# NanoRemotev2.net
KiCad netlist of a schematic drawn in EAGLE
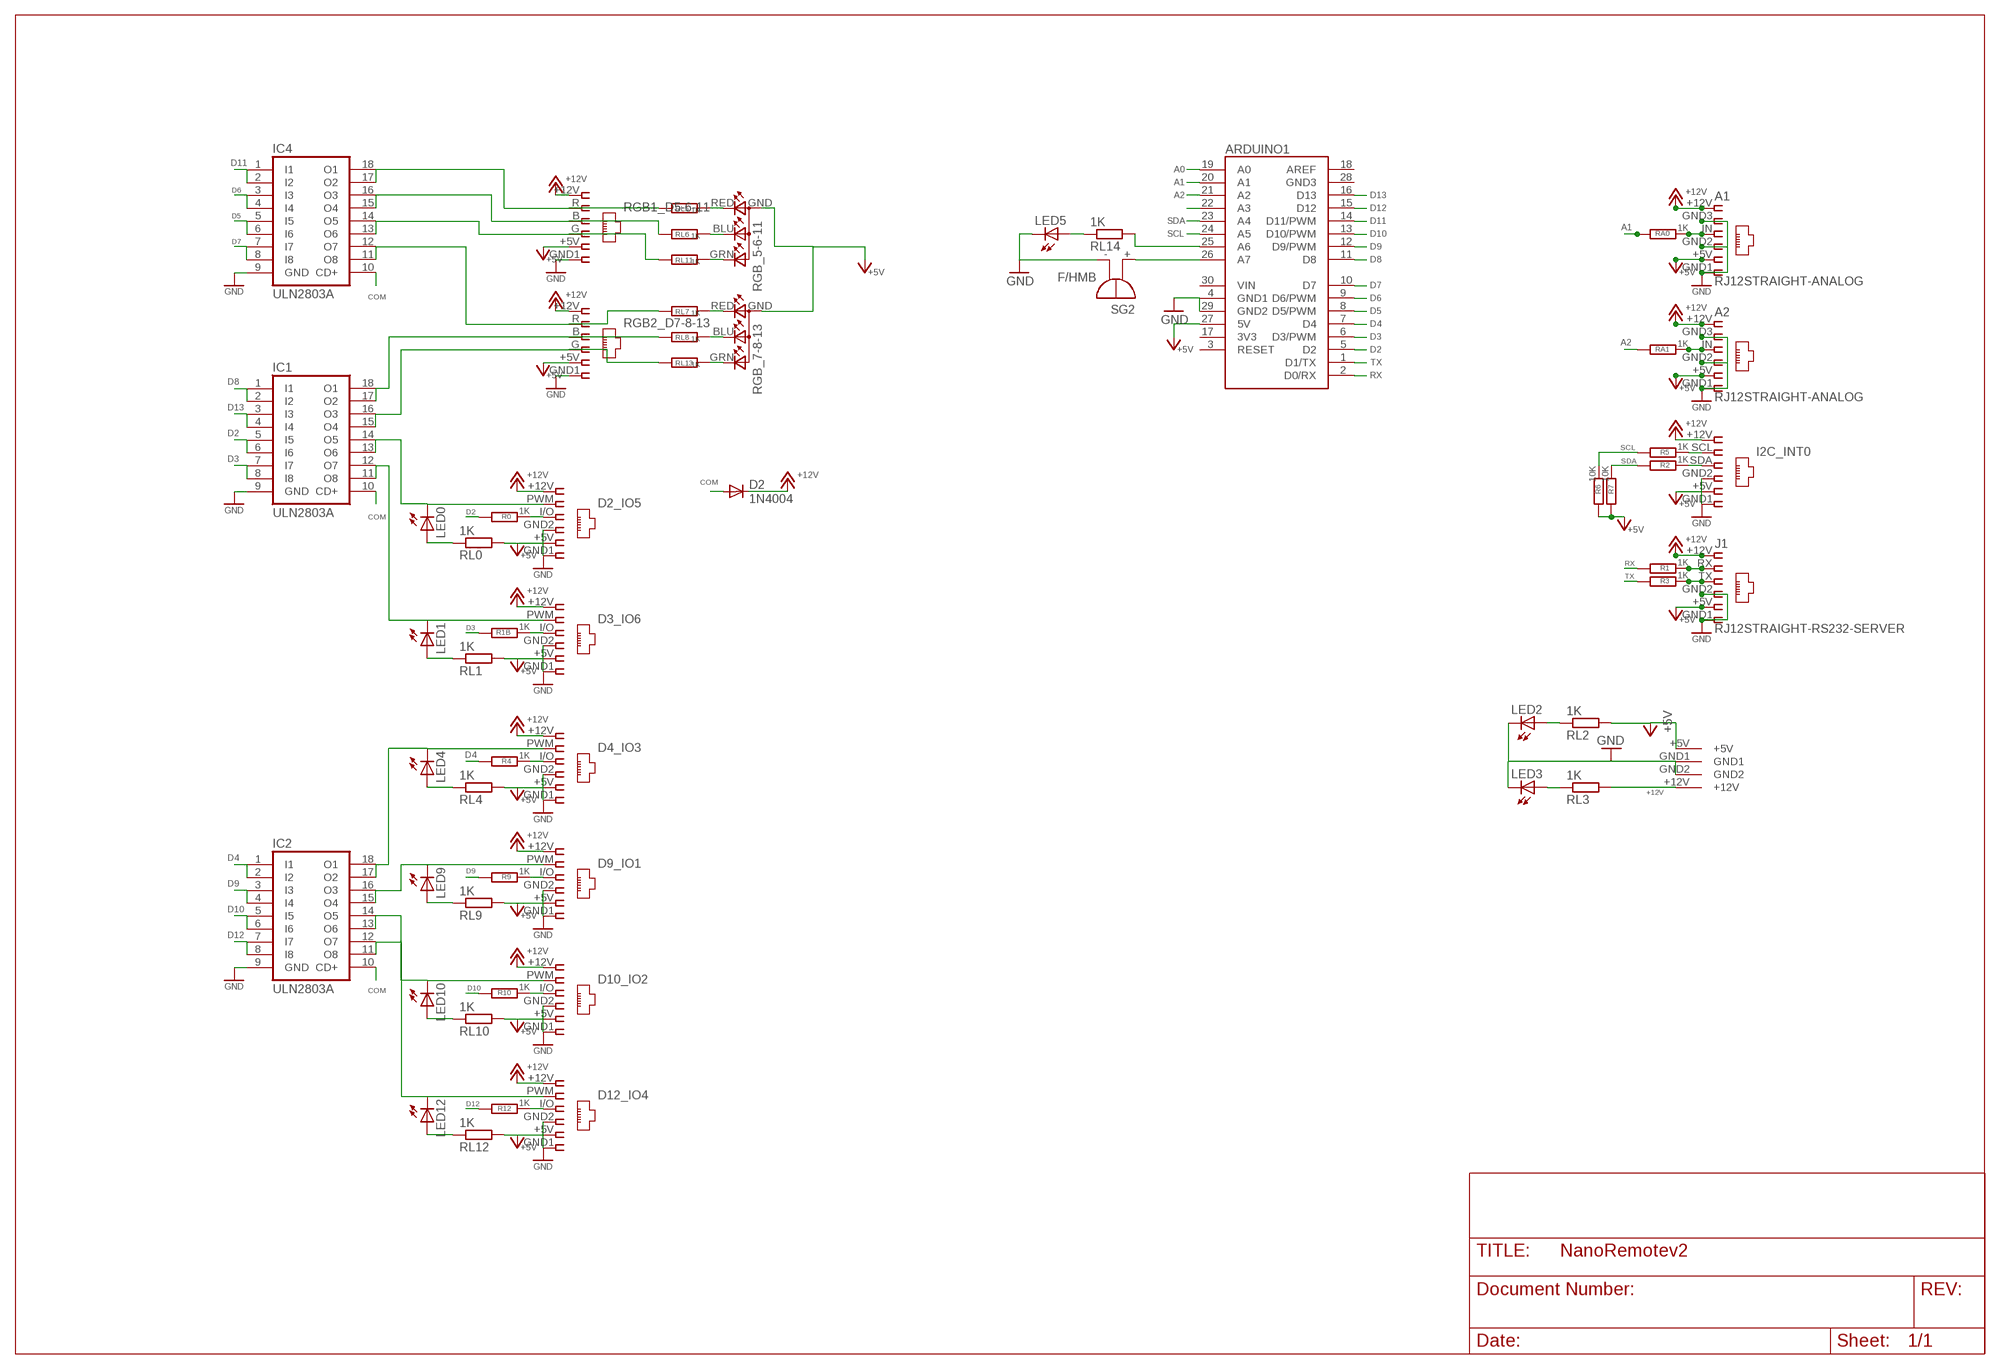
[diagram p0: schematic, sheet 1]

(export (version "E")
  (design (tool "Eeschema 10.0.6"))
  (components
    (comp (ref "A1")
      (value "RJ12STRAIGHT-ANALOG")
      (footprint "eagle-import:RJ12-STRAIGHT-ANALOG")
      (libsource (lib "eagle-import") (part "RJ12STRAIGHT-ANALOG"))
    )
    (comp (ref "A2")
      (value "RJ12STRAIGHT-ANALOG")
      (footprint "eagle-import:RJ12-STRAIGHT-ANALOG")
      (libsource (lib "eagle-import") (part "RJ12STRAIGHT-ANALOG"))
    )
    (comp (ref "ARDUINO1")
      (value "ARDUINO_NANO")
      (footprint "eagle-import:ARDUINO_NANO")
      (libsource (lib "eagle-import") (part "ARDUINO_NANO"))
    )
    (comp (ref "D2")
      (value "1N4004")
      (footprint "eagle-import:DO41-10")
      (libsource (lib "eagle-import") (part "1N4004"))
    )
    (comp (ref "D2_IO5")
      (value "IO5")
      (footprint "eagle-import:RJ12-STRAIGHT")
      (libsource (lib "eagle-import") (part "RJ12STRAIGHT"))
    )
    (comp (ref "D3_IO6")
      (value "IO6")
      (footprint "eagle-import:RJ12-STRAIGHT")
      (libsource (lib "eagle-import") (part "RJ12STRAIGHT"))
    )
    (comp (ref "D4_IO3")
      (value "IO3")
      (footprint "eagle-import:RJ12-STRAIGHT")
      (libsource (lib "eagle-import") (part "RJ12STRAIGHT"))
    )
    (comp (ref "D9_IO1")
      (value "IO1")
      (footprint "eagle-import:RJ12-STRAIGHT")
      (libsource (lib "eagle-import") (part "RJ12STRAIGHT"))
    )
    (comp (ref "D10_IO2")
      (value "IO2")
      (footprint "eagle-import:RJ12-STRAIGHT")
      (libsource (lib "eagle-import") (part "RJ12STRAIGHT"))
    )
    (comp (ref "D12_IO4")
      (value "IO4")
      (footprint "eagle-import:RJ12-STRAIGHT")
      (libsource (lib "eagle-import") (part "RJ12STRAIGHT"))
    )
    (comp (ref "I2C_INT0")
      (value "I2C")
      (footprint "eagle-import:RJ12-STRAIGHT-I2C")
      (libsource (lib "eagle-import") (part "RJ12STRAIGHT-I2C"))
    )
    (comp (ref "IC1")
      (value "ULN2803A")
      (footprint "eagle-import:SO18W")
      (libsource (lib "eagle-import") (part "ULN2803A"))
    )
    (comp (ref "IC2")
      (value "ULN2803A")
      (footprint "eagle-import:SO18W")
      (libsource (lib "eagle-import") (part "ULN2803A"))
    )
    (comp (ref "IC4")
      (value "ULN2803A")
      (footprint "eagle-import:SO18W")
      (libsource (lib "eagle-import") (part "ULN2803A"))
    )
    (comp (ref "J1")
      (value "RJ12STRAIGHT-RS232-SERVER")
      (footprint "eagle-import:RJ12-STRAIGHT-RS232")
      (libsource (lib "eagle-import") (part "RJ12STRAIGHT-RS232-SERVER"))
    )
    (comp (ref "LED0")
      (value "LED3MM")
      (footprint "eagle-import:LED3MM")
      (libsource (lib "eagle-import") (part "LED3MM"))
    )
    (comp (ref "LED1")
      (value "LED3MM")
      (footprint "eagle-import:LED3MM")
      (libsource (lib "eagle-import") (part "LED3MM"))
    )
    (comp (ref "LED2")
      (value "LED3MM")
      (footprint "eagle-import:LED3MM")
      (libsource (lib "eagle-import") (part "LED3MM"))
    )
    (comp (ref "LED3")
      (value "LED3MM")
      (footprint "eagle-import:LED3MM")
      (libsource (lib "eagle-import") (part "LED3MM"))
    )
    (comp (ref "LED4")
      (value "LED3MM")
      (footprint "eagle-import:LED3MM")
      (libsource (lib "eagle-import") (part "LED3MM"))
    )
    (comp (ref "LED5")
      (value "LED3MM")
      (footprint "eagle-import:LED3MM")
      (libsource (lib "eagle-import") (part "LED3MM"))
    )
    (comp (ref "LED9")
      (value "LED3MM")
      (footprint "eagle-import:LED3MM")
      (libsource (lib "eagle-import") (part "LED3MM"))
    )
    (comp (ref "LED10")
      (value "LED3MM")
      (footprint "eagle-import:LED3MM")
      (libsource (lib "eagle-import") (part "LED3MM"))
    )
    (comp (ref "LED12")
      (value "LED3MM")
      (footprint "eagle-import:LED3MM")
      (libsource (lib "eagle-import") (part "LED3MM"))
    )
    (comp (ref "R0")
      (value "1K")
      (footprint "eagle-import:M1206")
      (libsource (lib "eagle-import") (part "R-EU_M1206"))
    )
    (comp (ref "R1")
      (value "1K")
      (footprint "eagle-import:M1206")
      (libsource (lib "eagle-import") (part "R-EU_M1206"))
    )
    (comp (ref "R1B")
      (value "1K")
      (footprint "eagle-import:M1206")
      (libsource (lib "eagle-import") (part "R-EU_M1206"))
    )
    (comp (ref "R2")
      (value "1K")
      (footprint "eagle-import:M1206")
      (libsource (lib "eagle-import") (part "R-EU_M1206"))
    )
    (comp (ref "R3")
      (value "1K")
      (footprint "eagle-import:M1206")
      (libsource (lib "eagle-import") (part "R-EU_M1206"))
    )
    (comp (ref "R4")
      (value "1K")
      (footprint "eagle-import:M1206")
      (libsource (lib "eagle-import") (part "R-EU_M1206"))
    )
    (comp (ref "R5")
      (value "1K")
      (footprint "eagle-import:M1206")
      (libsource (lib "eagle-import") (part "R-EU_M1206"))
    )
    (comp (ref "R6")
      (value "10K")
      (footprint "eagle-import:M1206")
      (libsource (lib "eagle-import") (part "R-EU_M1206"))
    )
    (comp (ref "R7")
      (value "10K")
      (footprint "eagle-import:M1206")
      (libsource (lib "eagle-import") (part "R-EU_M1206"))
    )
    (comp (ref "R9")
      (value "1K")
      (footprint "eagle-import:M1206")
      (libsource (lib "eagle-import") (part "R-EU_M1206"))
    )
    (comp (ref "R10")
      (value "1K")
      (footprint "eagle-import:M1206")
      (libsource (lib "eagle-import") (part "R-EU_M1206"))
    )
    (comp (ref "R12")
      (value "1K")
      (footprint "eagle-import:M1206")
      (libsource (lib "eagle-import") (part "R-EU_M1206"))
    )
    (comp (ref "RA0")
      (value "1K")
      (footprint "eagle-import:M1206")
      (libsource (lib "eagle-import") (part "R-EU_M1206"))
    )
    (comp (ref "RA1")
      (value "1K")
      (footprint "eagle-import:M1206")
      (libsource (lib "eagle-import") (part "R-EU_M1206"))
    )
    (comp (ref "RGB1_D5-6-11")
      (value "RGB1")
      (footprint "eagle-import:RJ12-STRAIGHT-RGB")
      (libsource (lib "eagle-import") (part "RJ12STRAIGHT-RGB"))
    )
    (comp (ref "RGB2_D7-8-13")
      (value "RGB2")
      (footprint "eagle-import:RJ12-STRAIGHT-RGB")
      (libsource (lib "eagle-import") (part "RJ12STRAIGHT-RGB"))
    )
    (comp (ref "RGB_5-6-11")
      (value "TOPLED-3")
      (footprint "eagle-import:LED-TRICOLOR-THROUGHHOLE")
      (libsource (lib "eagle-import") (part "TOPLED-3"))
    )
    (comp (ref "RGB_7-8-13")
      (value "TOPLED-3")
      (footprint "eagle-import:LED-TRICOLOR-THROUGHHOLE")
      (libsource (lib "eagle-import") (part "TOPLED-3"))
    )
    (comp (ref "RL0")
      (value "1K")
      (footprint "eagle-import:M1206")
      (libsource (lib "eagle-import") (part "R-EU_M1206"))
    )
    (comp (ref "RL1")
      (value "1K")
      (footprint "eagle-import:M1206")
      (libsource (lib "eagle-import") (part "R-EU_M1206"))
    )
    (comp (ref "RL2")
      (value "1K")
      (footprint "eagle-import:M1206")
      (libsource (lib "eagle-import") (part "R-EU_M1206"))
    )
    (comp (ref "RL3")
      (value "1K")
      (footprint "eagle-import:M1206")
      (libsource (lib "eagle-import") (part "R-EU_M1206"))
    )
    (comp (ref "RL4")
      (value "1K")
      (footprint "eagle-import:M1206")
      (libsource (lib "eagle-import") (part "R-EU_M1206"))
    )
    (comp (ref "RL5")
      (value "1K")
      (footprint "eagle-import:M1206")
      (libsource (lib "eagle-import") (part "R-EU_M1206"))
    )
    (comp (ref "RL6")
      (value "1K")
      (footprint "eagle-import:M1206")
      (libsource (lib "eagle-import") (part "R-EU_M1206"))
    )
    (comp (ref "RL7")
      (value "1K")
      (footprint "eagle-import:M1206")
      (libsource (lib "eagle-import") (part "R-EU_M1206"))
    )
    (comp (ref "RL8")
      (value "1K")
      (footprint "eagle-import:M1206")
      (libsource (lib "eagle-import") (part "R-EU_M1206"))
    )
    (comp (ref "RL9")
      (value "1K")
      (footprint "eagle-import:M1206")
      (libsource (lib "eagle-import") (part "R-EU_M1206"))
    )
    (comp (ref "RL10")
      (value "1K")
      (footprint "eagle-import:M1206")
      (libsource (lib "eagle-import") (part "R-EU_M1206"))
    )
    (comp (ref "RL11")
      (value "1K")
      (footprint "eagle-import:M1206")
      (libsource (lib "eagle-import") (part "R-EU_M1206"))
    )
    (comp (ref "RL12")
      (value "1K")
      (footprint "eagle-import:M1206")
      (libsource (lib "eagle-import") (part "R-EU_M1206"))
    )
    (comp (ref "RL13")
      (value "1K")
      (footprint "eagle-import:M1206")
      (libsource (lib "eagle-import") (part "R-EU_M1206"))
    )
    (comp (ref "RL14")
      (value "1K")
      (footprint "eagle-import:M1206")
      (libsource (lib "eagle-import") (part "R-EU_M1206"))
    )
    (comp (ref "SG2")
      (value "F/HMB")
      (footprint "eagle-import:F_HMB")
      (libsource (lib "eagle-import") (part "F/HMB"))
    )
    (comp (ref "U$1")
      (value "KPJX-4S-S")
      (footprint "eagle-import:KPJX-4S-S")
      (libsource (lib "eagle-import") (part "KPJX-4S-S"))
    )
  )
  (nets
    (net (code "1") (name "+5V") (class "Default")
      (node (ref "A1") (pin "+5V") (pinfunction "5_+5V") (pintype "power_in"))
      (node (ref "A2") (pin "+5V") (pinfunction "5_+5V") (pintype "power_in"))
      (node (ref "ARDUINO1") (pin "27") (pinfunction "5V_27") (pintype "power_in"))
      (node (ref "D10_IO2") (pin "+5V") (pinfunction "5_+5V") (pintype "power_in"))
      (node (ref "D12_IO4") (pin "+5V") (pinfunction "5_+5V") (pintype "power_in"))
      (node (ref "D2_IO5") (pin "+5V") (pinfunction "5_+5V") (pintype "power_in"))
      (node (ref "D3_IO6") (pin "+5V") (pinfunction "5_+5V") (pintype "power_in"))
      (node (ref "D4_IO3") (pin "+5V") (pinfunction "5_+5V") (pintype "power_in"))
      (node (ref "D9_IO1") (pin "+5V") (pinfunction "5_+5V") (pintype "power_in"))
      (node (ref "I2C_INT0") (pin "+5V") (pinfunction "5_+5V") (pintype "power_in"))
      (node (ref "J1") (pin "+5V") (pinfunction "5_+5V") (pintype "power_in"))
      (node (ref "R6") (pin "2") (pinfunction "2_2") (pintype "passive"))
      (node (ref "R7") (pin "2") (pinfunction "2_2") (pintype "passive"))
      (node (ref "RGB1_D5-6-11") (pin "+5V") (pinfunction "5_+5V") (pintype "power_in"))
      (node (ref "RGB2_D7-8-13") (pin "+5V") (pinfunction "5_+5V") (pintype "power_in"))
      (node (ref "RGB_5-6-11") (pin "GND") (pinfunction "A2_GND") (pintype "passive"))
      (node (ref "RGB_7-8-13") (pin "GND") (pinfunction "A2_GND") (pintype "passive"))
      (node (ref "RL0") (pin "2") (pinfunction "2_2") (pintype "passive"))
      (node (ref "RL1") (pin "2") (pinfunction "2_2") (pintype "passive"))
      (node (ref "RL10") (pin "2") (pinfunction "2_2") (pintype "passive"))
      (node (ref "RL12") (pin "2") (pinfunction "2_2") (pintype "passive"))
      (node (ref "RL2") (pin "2") (pinfunction "2_2") (pintype "passive"))
      (node (ref "RL4") (pin "2") (pinfunction "2_2") (pintype "passive"))
      (node (ref "RL9") (pin "2") (pinfunction "2_2") (pintype "passive"))
      (node (ref "U$1") (pin "+5V") (pinfunction "+5V_+5V") (pintype "power_in"))
    )
    (net (code "2") (name "+12V") (class "Default")
      (node (ref "A1") (pin "+12V") (pinfunction "1_+12V") (pintype "power_in"))
      (node (ref "A2") (pin "+12V") (pinfunction "1_+12V") (pintype "power_in"))
      (node (ref "D10_IO2") (pin "+12V") (pinfunction "1_+12V") (pintype "power_in"))
      (node (ref "D12_IO4") (pin "+12V") (pinfunction "1_+12V") (pintype "power_in"))
      (node (ref "D2") (pin "C") (pinfunction "C_C") (pintype "passive"))
      (node (ref "D2_IO5") (pin "+12V") (pinfunction "1_+12V") (pintype "power_in"))
      (node (ref "D3_IO6") (pin "+12V") (pinfunction "1_+12V") (pintype "power_in"))
      (node (ref "D4_IO3") (pin "+12V") (pinfunction "1_+12V") (pintype "power_in"))
      (node (ref "D9_IO1") (pin "+12V") (pinfunction "1_+12V") (pintype "power_in"))
      (node (ref "I2C_INT0") (pin "+12V") (pinfunction "1_+12V") (pintype "power_in"))
      (node (ref "J1") (pin "+12V") (pinfunction "1_+12V") (pintype "power_in"))
      (node (ref "RGB1_D5-6-11") (pin "+12V") (pinfunction "1_+12V") (pintype "power_in"))
      (node (ref "RGB2_D7-8-13") (pin "+12V") (pinfunction "1_+12V") (pintype "power_in"))
      (node (ref "RL3") (pin "2") (pinfunction "2_2") (pintype "passive"))
      (node (ref "U$1") (pin "+12V") (pinfunction "+12V_+12V") (pintype "power_in"))
    )
    (net (code "3") (name "/3V3") (class "Default")
      (node (ref "ARDUINO1") (pin "17") (pinfunction "3V3_17") (pintype "power_in"))
    )
    (net (code "4") (name "/A0") (class "Default")
      (node (ref "ARDUINO1") (pin "19") (pinfunction "A0_19") (pintype "bidirectional"))
    )
    (net (code "5") (name "/A1") (class "Default")
      (node (ref "ARDUINO1") (pin "20") (pinfunction "A1_20") (pintype "bidirectional"))
      (node (ref "RA0") (pin "2") (pinfunction "2_2") (pintype "passive"))
    )
    (net (code "6") (name "/A2") (class "Default")
      (node (ref "ARDUINO1") (pin "21") (pinfunction "A2_21") (pintype "bidirectional"))
      (node (ref "RA1") (pin "2") (pinfunction "2_2") (pintype "passive"))
    )
    (net (code "7") (name "/COM") (class "Default")
      (node (ref "D2") (pin "A") (pinfunction "A_A") (pintype "passive"))
      (node (ref "IC1") (pin "10") (pinfunction "CD+_10") (pintype "passive"))
      (node (ref "IC2") (pin "10") (pinfunction "CD+_10") (pintype "passive"))
      (node (ref "IC4") (pin "10") (pinfunction "CD+_10") (pintype "passive"))
    )
    (net (code "8") (name "/D2") (class "Default")
      (node (ref "ARDUINO1") (pin "5") (pinfunction "D2_5") (pintype "bidirectional"))
      (node (ref "IC1") (pin "5") (pinfunction "I5_5") (pintype "input"))
      (node (ref "IC1") (pin "6") (pinfunction "I6_6") (pintype "input"))
      (node (ref "R0") (pin "2") (pinfunction "2_2") (pintype "passive"))
    )
    (net (code "9") (name "/D3") (class "Default")
      (node (ref "ARDUINO1") (pin "6") (pinfunction "D3/PWM_6") (pintype "bidirectional"))
      (node (ref "IC1") (pin "7") (pinfunction "I7_7") (pintype "input"))
      (node (ref "IC1") (pin "8") (pinfunction "I8_8") (pintype "input"))
      (node (ref "R1B") (pin "2") (pinfunction "2_2") (pintype "passive"))
    )
    (net (code "10") (name "/D4") (class "Default")
      (node (ref "ARDUINO1") (pin "7") (pinfunction "D4_7") (pintype "bidirectional"))
      (node (ref "IC2") (pin "1") (pinfunction "I1_1") (pintype "input"))
      (node (ref "IC2") (pin "2") (pinfunction "I2_2") (pintype "input"))
      (node (ref "R4") (pin "2") (pinfunction "2_2") (pintype "passive"))
    )
    (net (code "11") (name "/D5") (class "Default")
      (node (ref "ARDUINO1") (pin "8") (pinfunction "D5/PWM_8") (pintype "bidirectional"))
      (node (ref "IC4") (pin "5") (pinfunction "I5_5") (pintype "input"))
      (node (ref "IC4") (pin "6") (pinfunction "I6_6") (pintype "input"))
    )
    (net (code "12") (name "/D6") (class "Default")
      (node (ref "ARDUINO1") (pin "9") (pinfunction "D6/PWM_9") (pintype "bidirectional"))
      (node (ref "IC4") (pin "3") (pinfunction "I3_3") (pintype "input"))
      (node (ref "IC4") (pin "4") (pinfunction "I4_4") (pintype "input"))
    )
    (net (code "13") (name "/D7") (class "Default")
      (node (ref "ARDUINO1") (pin "10") (pinfunction "D7_10") (pintype "bidirectional"))
      (node (ref "IC4") (pin "7") (pinfunction "I7_7") (pintype "input"))
      (node (ref "IC4") (pin "8") (pinfunction "I8_8") (pintype "input"))
    )
    (net (code "14") (name "/D8") (class "Default")
      (node (ref "ARDUINO1") (pin "11") (pinfunction "D8_11") (pintype "bidirectional"))
      (node (ref "IC1") (pin "1") (pinfunction "I1_1") (pintype "input"))
      (node (ref "IC1") (pin "2") (pinfunction "I2_2") (pintype "input"))
    )
    (net (code "15") (name "/D9") (class "Default")
      (node (ref "ARDUINO1") (pin "12") (pinfunction "D9/PWM_12") (pintype "bidirectional"))
      (node (ref "IC2") (pin "3") (pinfunction "I3_3") (pintype "input"))
      (node (ref "IC2") (pin "4") (pinfunction "I4_4") (pintype "input"))
      (node (ref "R9") (pin "2") (pinfunction "2_2") (pintype "passive"))
    )
    (net (code "16") (name "/D10") (class "Default")
      (node (ref "ARDUINO1") (pin "13") (pinfunction "D10/PWM_13") (pintype "bidirectional"))
      (node (ref "IC2") (pin "5") (pinfunction "I5_5") (pintype "input"))
      (node (ref "IC2") (pin "6") (pinfunction "I6_6") (pintype "input"))
      (node (ref "R10") (pin "2") (pinfunction "2_2") (pintype "passive"))
    )
    (net (code "17") (name "/D11") (class "Default")
      (node (ref "ARDUINO1") (pin "14") (pinfunction "D11/PWM_14") (pintype "bidirectional"))
      (node (ref "IC4") (pin "1") (pinfunction "I1_1") (pintype "input"))
      (node (ref "IC4") (pin "2") (pinfunction "I2_2") (pintype "input"))
    )
    (net (code "18") (name "/D12") (class "Default")
      (node (ref "ARDUINO1") (pin "15") (pinfunction "D12_15") (pintype "bidirectional"))
      (node (ref "IC2") (pin "7") (pinfunction "I7_7") (pintype "input"))
      (node (ref "IC2") (pin "8") (pinfunction "I8_8") (pintype "input"))
      (node (ref "R12") (pin "2") (pinfunction "2_2") (pintype "passive"))
    )
    (net (code "19") (name "/D13") (class "Default")
      (node (ref "ARDUINO1") (pin "16") (pinfunction "D13_16") (pintype "bidirectional"))
      (node (ref "IC1") (pin "3") (pinfunction "I3_3") (pintype "input"))
      (node (ref "IC1") (pin "4") (pinfunction "I4_4") (pintype "input"))
    )
    (net (code "20") (name "/RX") (class "Default")
      (node (ref "ARDUINO1") (pin "2") (pinfunction "D0/RX_2") (pintype "bidirectional"))
      (node (ref "R1") (pin "2") (pinfunction "2_2") (pintype "passive"))
    )
    (net (code "21") (name "/SCL") (class "Default")
      (node (ref "ARDUINO1") (pin "24") (pinfunction "A5_24") (pintype "bidirectional"))
      (node (ref "R5") (pin "2") (pinfunction "2_2") (pintype "passive"))
      (node (ref "R6") (pin "1") (pinfunction "1_1") (pintype "passive"))
    )
    (net (code "22") (name "/SDA") (class "Default")
      (node (ref "ARDUINO1") (pin "23") (pinfunction "A4_23") (pintype "bidirectional"))
      (node (ref "R2") (pin "2") (pinfunction "2_2") (pintype "passive"))
      (node (ref "R7") (pin "1") (pinfunction "1_1") (pintype "passive"))
    )
    (net (code "23") (name "/TX") (class "Default")
      (node (ref "ARDUINO1") (pin "1") (pinfunction "D1/TX_1") (pintype "bidirectional"))
      (node (ref "R3") (pin "2") (pinfunction "2_2") (pintype "passive"))
    )
    (net (code "24") (name "GND") (class "Default")
      (node (ref "A1") (pin "GND1") (pinfunction "6_GND1") (pintype "power_in"))
      (node (ref "A1") (pin "GND2") (pinfunction "4_GND2") (pintype "power_in"))
      (node (ref "A1") (pin "GND3") (pinfunction "2_GND3") (pintype "bidirectional"))
      (node (ref "A2") (pin "GND1") (pinfunction "6_GND1") (pintype "power_in"))
      (node (ref "A2") (pin "GND2") (pinfunction "4_GND2") (pintype "power_in"))
      (node (ref "A2") (pin "GND3") (pinfunction "2_GND3") (pintype "bidirectional"))
      (node (ref "ARDUINO1") (pin "29") (pinfunction "GND2_29") (pintype "power_in"))
      (node (ref "ARDUINO1") (pin "4") (pinfunction "GND1_4") (pintype "power_in"))
      (node (ref "D10_IO2") (pin "GND1") (pinfunction "6_GND1") (pintype "power_in"))
      (node (ref "D10_IO2") (pin "GND2") (pinfunction "4_GND2") (pintype "power_in"))
      (node (ref "D12_IO4") (pin "GND1") (pinfunction "6_GND1") (pintype "power_in"))
      (node (ref "D12_IO4") (pin "GND2") (pinfunction "4_GND2") (pintype "power_in"))
      (node (ref "D2_IO5") (pin "GND1") (pinfunction "6_GND1") (pintype "power_in"))
      (node (ref "D2_IO5") (pin "GND2") (pinfunction "4_GND2") (pintype "power_in"))
      (node (ref "D3_IO6") (pin "GND1") (pinfunction "6_GND1") (pintype "power_in"))
      (node (ref "D3_IO6") (pin "GND2") (pinfunction "4_GND2") (pintype "power_in"))
      (node (ref "D4_IO3") (pin "GND1") (pinfunction "6_GND1") (pintype "power_in"))
      (node (ref "D4_IO3") (pin "GND2") (pinfunction "4_GND2") (pintype "power_in"))
      (node (ref "D9_IO1") (pin "GND1") (pinfunction "6_GND1") (pintype "power_in"))
      (node (ref "D9_IO1") (pin "GND2") (pinfunction "4_GND2") (pintype "power_in"))
      (node (ref "I2C_INT0") (pin "GND1") (pinfunction "6_GND1") (pintype "power_in"))
      (node (ref "I2C_INT0") (pin "GND2") (pinfunction "4_GND2") (pintype "power_in"))
      (node (ref "IC1") (pin "9") (pinfunction "GND_9") (pintype "power_in"))
      (node (ref "IC2") (pin "9") (pinfunction "GND_9") (pintype "power_in"))
      (node (ref "IC4") (pin "9") (pinfunction "GND_9") (pintype "power_in"))
      (node (ref "J1") (pin "GND1") (pinfunction "6_GND1") (pintype "power_in"))
      (node (ref "J1") (pin "GND2") (pinfunction "4_GND2") (pintype "power_in"))
      (node (ref "LED2") (pin "K") (pinfunction "C_K") (pintype "passive"))
      (node (ref "LED3") (pin "K") (pinfunction "C_K") (pintype "passive"))
      (node (ref "LED5") (pin "K") (pinfunction "C_K") (pintype "passive"))
      (node (ref "RGB1_D5-6-11") (pin "GND1") (pinfunction "6_GND1") (pintype "power_in"))
      (node (ref "RGB2_D7-8-13") (pin "GND1") (pinfunction "6_GND1") (pintype "power_in"))
      (node (ref "SG2") (pin "-") (pinfunction "-_-") (pintype "passive"))
      (node (ref "U$1") (pin "GND1") (pinfunction "GND1_GND1") (pintype "input"))
      (node (ref "U$1") (pin "GND2") (pinfunction "GND2_GND2") (pintype "input"))
    )
    (net (code "25") (name "Net-(A1-3)") (class "Default")
      (node (ref "A1") (pin "IN") (pinfunction "3_IN") (pintype "bidirectional"))
      (node (ref "RA0") (pin "1") (pinfunction "1_1") (pintype "passive"))
    )
    (net (code "26") (name "Net-(A2-3)") (class "Default")
      (node (ref "A2") (pin "IN") (pinfunction "3_IN") (pintype "bidirectional"))
      (node (ref "RA1") (pin "1") (pinfunction "1_1") (pintype "passive"))
    )
    (net (code "27") (name "Net-(ARDUINO1-A6)") (class "Default")
      (node (ref "ARDUINO1") (pin "25") (pinfunction "A6_25") (pintype "bidirectional"))
      (node (ref "RL14") (pin "2") (pinfunction "2_2") (pintype "passive"))
    )
    (net (code "28") (name "Net-(ARDUINO1-A7)") (class "Default")
      (node (ref "ARDUINO1") (pin "26") (pinfunction "A7_26") (pintype "bidirectional"))
      (node (ref "SG2") (pin "+") (pinfunction "+_+") (pintype "passive"))
    )
    (net (code "29") (name "Net-(D2_IO5-2)") (class "Default")
      (node (ref "D2_IO5") (pin "PWM") (pinfunction "2_PWM") (pintype "bidirectional"))
      (node (ref "IC1") (pin "13") (pinfunction "O6_13") (pintype "open_collector"))
      (node (ref "IC1") (pin "14") (pinfunction "O5_14") (pintype "open_collector"))
      (node (ref "LED0") (pin "K") (pinfunction "C_K") (pintype "passive"))
    )
    (net (code "30") (name "Net-(D2_IO5-3)") (class "Default")
      (node (ref "D2_IO5") (pin "I/O") (pinfunction "3_I/O") (pintype "bidirectional"))
      (node (ref "R0") (pin "1") (pinfunction "1_1") (pintype "passive"))
    )
    (net (code "31") (name "Net-(D3_IO6-2)") (class "Default")
      (node (ref "D3_IO6") (pin "PWM") (pinfunction "2_PWM") (pintype "bidirectional"))
      (node (ref "IC1") (pin "11") (pinfunction "O8_11") (pintype "open_collector"))
      (node (ref "IC1") (pin "12") (pinfunction "O7_12") (pintype "open_collector"))
      (node (ref "LED1") (pin "K") (pinfunction "C_K") (pintype "passive"))
    )
    (net (code "32") (name "Net-(D3_IO6-3)") (class "Default")
      (node (ref "D3_IO6") (pin "I/O") (pinfunction "3_I/O") (pintype "bidirectional"))
      (node (ref "R1B") (pin "1") (pinfunction "1_1") (pintype "passive"))
    )
    (net (code "33") (name "Net-(D4_IO3-2)") (class "Default")
      (node (ref "D4_IO3") (pin "PWM") (pinfunction "2_PWM") (pintype "bidirectional"))
      (node (ref "IC2") (pin "17") (pinfunction "O2_17") (pintype "open_collector"))
      (node (ref "IC2") (pin "18") (pinfunction "O1_18") (pintype "open_collector"))
      (node (ref "LED4") (pin "K") (pinfunction "C_K") (pintype "passive"))
    )
    (net (code "34") (name "Net-(D4_IO3-3)") (class "Default")
      (node (ref "D4_IO3") (pin "I/O") (pinfunction "3_I/O") (pintype "bidirectional"))
      (node (ref "R4") (pin "1") (pinfunction "1_1") (pintype "passive"))
    )
    (net (code "35") (name "Net-(D9_IO1-2)") (class "Default")
      (node (ref "D9_IO1") (pin "PWM") (pinfunction "2_PWM") (pintype "bidirectional"))
      (node (ref "IC2") (pin "15") (pinfunction "O4_15") (pintype "open_collector"))
      (node (ref "IC2") (pin "16") (pinfunction "O3_16") (pintype "open_collector"))
      (node (ref "LED9") (pin "K") (pinfunction "C_K") (pintype "passive"))
    )
    (net (code "36") (name "Net-(D9_IO1-3)") (class "Default")
      (node (ref "D9_IO1") (pin "I/O") (pinfunction "3_I/O") (pintype "bidirectional"))
      (node (ref "R9") (pin "1") (pinfunction "1_1") (pintype "passive"))
    )
    (net (code "37") (name "Net-(D10_IO2-2)") (class "Default")
      (node (ref "D10_IO2") (pin "PWM") (pinfunction "2_PWM") (pintype "bidirectional"))
      (node (ref "IC2") (pin "13") (pinfunction "O6_13") (pintype "open_collector"))
      (node (ref "IC2") (pin "14") (pinfunction "O5_14") (pintype "open_collector"))
      (node (ref "LED10") (pin "K") (pinfunction "C_K") (pintype "passive"))
    )
    (net (code "38") (name "Net-(D10_IO2-3)") (class "Default")
      (node (ref "D10_IO2") (pin "I/O") (pinfunction "3_I/O") (pintype "bidirectional"))
      (node (ref "R10") (pin "1") (pinfunction "1_1") (pintype "passive"))
    )
    (net (code "39") (name "Net-(D12_IO4-2)") (class "Default")
      (node (ref "D12_IO4") (pin "PWM") (pinfunction "2_PWM") (pintype "bidirectional"))
      (node (ref "IC2") (pin "11") (pinfunction "O8_11") (pintype "open_collector"))
      (node (ref "IC2") (pin "12") (pinfunction "O7_12") (pintype "open_collector"))
      (node (ref "LED12") (pin "K") (pinfunction "C_K") (pintype "passive"))
    )
    (net (code "40") (name "Net-(D12_IO4-3)") (class "Default")
      (node (ref "D12_IO4") (pin "I/O") (pinfunction "3_I/O") (pintype "bidirectional"))
      (node (ref "R12") (pin "1") (pinfunction "1_1") (pintype "passive"))
    )
    (net (code "41") (name "Net-(I2C_INT0-2)") (class "Default")
      (node (ref "I2C_INT0") (pin "SCL") (pinfunction "2_SCL") (pintype "bidirectional"))
      (node (ref "R5") (pin "1") (pinfunction "1_1") (pintype "passive"))
    )
    (net (code "42") (name "Net-(I2C_INT0-3)") (class "Default")
      (node (ref "I2C_INT0") (pin "SDA") (pinfunction "3_SDA") (pintype "bidirectional"))
      (node (ref "R2") (pin "1") (pinfunction "1_1") (pintype "passive"))
    )
    (net (code "43") (name "Net-(IC1-O1)") (class "Default")
      (node (ref "IC1") (pin "17") (pinfunction "O2_17") (pintype "open_collector"))
      (node (ref "IC1") (pin "18") (pinfunction "O1_18") (pintype "open_collector"))
      (node (ref "RGB2_D7-8-13") (pin "B") (pinfunction "3_B") (pintype "bidirectional"))
      (node (ref "RL8") (pin "1") (pinfunction "1_1") (pintype "passive"))
    )
    (net (code "44") (name "Net-(IC1-O3)") (class "Default")
      (node (ref "IC1") (pin "15") (pinfunction "O4_15") (pintype "open_collector"))
      (node (ref "IC1") (pin "16") (pinfunction "O3_16") (pintype "open_collector"))
      (node (ref "RGB2_D7-8-13") (pin "G") (pinfunction "4_G") (pintype "power_in"))
      (node (ref "RL13") (pin "1") (pinfunction "1_1") (pintype "passive"))
    )
    (net (code "45") (name "Net-(IC4-O1)") (class "Default")
      (node (ref "IC4") (pin "17") (pinfunction "O2_17") (pintype "open_collector"))
      (node (ref "IC4") (pin "18") (pinfunction "O1_18") (pintype "open_collector"))
      (node (ref "RGB1_D5-6-11") (pin "R") (pinfunction "2_R") (pintype "bidirectional"))
      (node (ref "RL5") (pin "1") (pinfunction "1_1") (pintype "passive"))
    )
    (net (code "46") (name "Net-(IC4-O3)") (class "Default")
      (node (ref "IC4") (pin "15") (pinfunction "O4_15") (pintype "open_collector"))
      (node (ref "IC4") (pin "16") (pinfunction "O3_16") (pintype "open_collector"))
      (node (ref "RGB1_D5-6-11") (pin "B") (pinfunction "3_B") (pintype "bidirectional"))
      (node (ref "RL6") (pin "1") (pinfunction "1_1") (pintype "passive"))
    )
    (net (code "47") (name "Net-(IC4-O5)") (class "Default")
      (node (ref "IC4") (pin "13") (pinfunction "O6_13") (pintype "open_collector"))
      (node (ref "IC4") (pin "14") (pinfunction "O5_14") (pintype "open_collector"))
      (node (ref "RGB1_D5-6-11") (pin "G") (pinfunction "4_G") (pintype "power_in"))
      (node (ref "RL11") (pin "1") (pinfunction "1_1") (pintype "passive"))
    )
    (net (code "48") (name "Net-(IC4-O7)") (class "Default")
      (node (ref "IC4") (pin "11") (pinfunction "O8_11") (pintype "open_collector"))
      (node (ref "IC4") (pin "12") (pinfunction "O7_12") (pintype "open_collector"))
      (node (ref "RGB2_D7-8-13") (pin "R") (pinfunction "2_R") (pintype "bidirectional"))
      (node (ref "RL7") (pin "1") (pinfunction "1_1") (pintype "passive"))
    )
    (net (code "49") (name "Net-(J1-2)") (class "Default")
      (node (ref "J1") (pin "RX") (pinfunction "2_RX") (pintype "bidirectional"))
      (node (ref "R1") (pin "1") (pinfunction "1_1") (pintype "passive"))
    )
    (net (code "50") (name "Net-(J1-3)") (class "Default")
      (node (ref "J1") (pin "TX") (pinfunction "3_TX") (pintype "bidirectional"))
      (node (ref "R3") (pin "1") (pinfunction "1_1") (pintype "passive"))
    )
    (net (code "51") (name "Net-(LED0-PadA)") (class "Default")
      (node (ref "LED0") (pin "A") (pinfunction "A_A") (pintype "passive"))
      (node (ref "RL0") (pin "1") (pinfunction "1_1") (pintype "passive"))
    )
    (net (code "52") (name "Net-(LED1-PadA)") (class "Default")
      (node (ref "LED1") (pin "A") (pinfunction "A_A") (pintype "passive"))
      (node (ref "RL1") (pin "1") (pinfunction "1_1") (pintype "passive"))
    )
    (net (code "53") (name "Net-(LED2-PadA)") (class "Default")
      (node (ref "LED2") (pin "A") (pinfunction "A_A") (pintype "passive"))
      (node (ref "RL2") (pin "1") (pinfunction "1_1") (pintype "passive"))
    )
    (net (code "54") (name "Net-(LED3-PadA)") (class "Default")
      (node (ref "LED3") (pin "A") (pinfunction "A_A") (pintype "passive"))
      (node (ref "RL3") (pin "1") (pinfunction "1_1") (pintype "passive"))
    )
    (net (code "55") (name "Net-(LED4-PadA)") (class "Default")
      (node (ref "LED4") (pin "A") (pinfunction "A_A") (pintype "passive"))
      (node (ref "RL4") (pin "1") (pinfunction "1_1") (pintype "passive"))
    )
    (net (code "56") (name "Net-(LED5-PadA)") (class "Default")
      (node (ref "LED5") (pin "A") (pinfunction "A_A") (pintype "passive"))
      (node (ref "RL14") (pin "1") (pinfunction "1_1") (pintype "passive"))
    )
    (net (code "57") (name "Net-(LED9-PadA)") (class "Default")
      (node (ref "LED9") (pin "A") (pinfunction "A_A") (pintype "passive"))
      (node (ref "RL9") (pin "1") (pinfunction "1_1") (pintype "passive"))
    )
    (net (code "58") (name "Net-(LED10-PadA)") (class "Default")
      (node (ref "LED10") (pin "A") (pinfunction "A_A") (pintype "passive"))
      (node (ref "RL10") (pin "1") (pinfunction "1_1") (pintype "passive"))
    )
    (net (code "59") (name "Net-(LED12-PadA)") (class "Default")
      (node (ref "LED12") (pin "A") (pinfunction "A_A") (pintype "passive"))
      (node (ref "RL12") (pin "1") (pinfunction "1_1") (pintype "passive"))
    )
    (net (code "60") (name "Net-(RGB_5-6-11-CBLUE)") (class "Default")
      (node (ref "RGB_5-6-11") (pin "BLU") (pinfunction "CBLUE_BLU") (pintype "passive"))
      (node (ref "RL6") (pin "2") (pinfunction "2_2") (pintype "passive"))
    )
    (net (code "61") (name "Net-(RGB_5-6-11-CGREEN)") (class "Default")
      (node (ref "RGB_5-6-11") (pin "GRN") (pinfunction "CGREEN_GRN") (pintype "passive"))
      (node (ref "RL11") (pin "2") (pinfunction "2_2") (pintype "passive"))
    )
    (net (code "62") (name "Net-(RGB_5-6-11-CRED)") (class "Default")
      (node (ref "RGB_5-6-11") (pin "RED") (pinfunction "CRED_RED") (pintype "passive"))
      (node (ref "RL5") (pin "2") (pinfunction "2_2") (pintype "passive"))
    )
    (net (code "63") (name "Net-(RGB_7-8-13-CBLUE)") (class "Default")
      (node (ref "RGB_7-8-13") (pin "BLU") (pinfunction "CBLUE_BLU") (pintype "passive"))
      (node (ref "RL8") (pin "2") (pinfunction "2_2") (pintype "passive"))
    )
    (net (code "64") (name "Net-(RGB_7-8-13-CGREEN)") (class "Default")
      (node (ref "RGB_7-8-13") (pin "GRN") (pinfunction "CGREEN_GRN") (pintype "passive"))
      (node (ref "RL13") (pin "2") (pinfunction "2_2") (pintype "passive"))
    )
    (net (code "65") (name "Net-(RGB_7-8-13-CRED)") (class "Default")
      (node (ref "RGB_7-8-13") (pin "RED") (pinfunction "CRED_RED") (pintype "passive"))
      (node (ref "RL7") (pin "2") (pinfunction "2_2") (pintype "passive"))
    )
    (net (code "66") (name "unconnected-(ARDUINO1-A3-Pad22)") (class "Default")
      (node (ref "ARDUINO1") (pin "22") (pinfunction "A3_22") (pintype "bidirectional"))
    )
    (net (code "67") (name "unconnected-(ARDUINO1-AREF-Pad18)") (class "Default")
      (node (ref "ARDUINO1") (pin "18") (pinfunction "AREF_18") (pintype "bidirectional"))
    )
    (net (code "68") (name "unconnected-(ARDUINO1-GND3-Pad28)") (class "Default")
      (node (ref "ARDUINO1") (pin "28") (pinfunction "GND3_28") (pintype "bidirectional"))
    )
    (net (code "69") (name "unconnected-(ARDUINO1-RESET-Pad3)") (class "Default")
      (node (ref "ARDUINO1") (pin "3") (pinfunction "RESET_3") (pintype "bidirectional"))
    )
    (net (code "70") (name "unconnected-(ARDUINO1-VIN-Pad30)") (class "Default")
      (node (ref "ARDUINO1") (pin "30") (pinfunction "VIN_30") (pintype "bidirectional"))
    )
  )
)
